# LED-mini35-SHIM.net
KiCad netlist of a schematic drawn in EAGLE
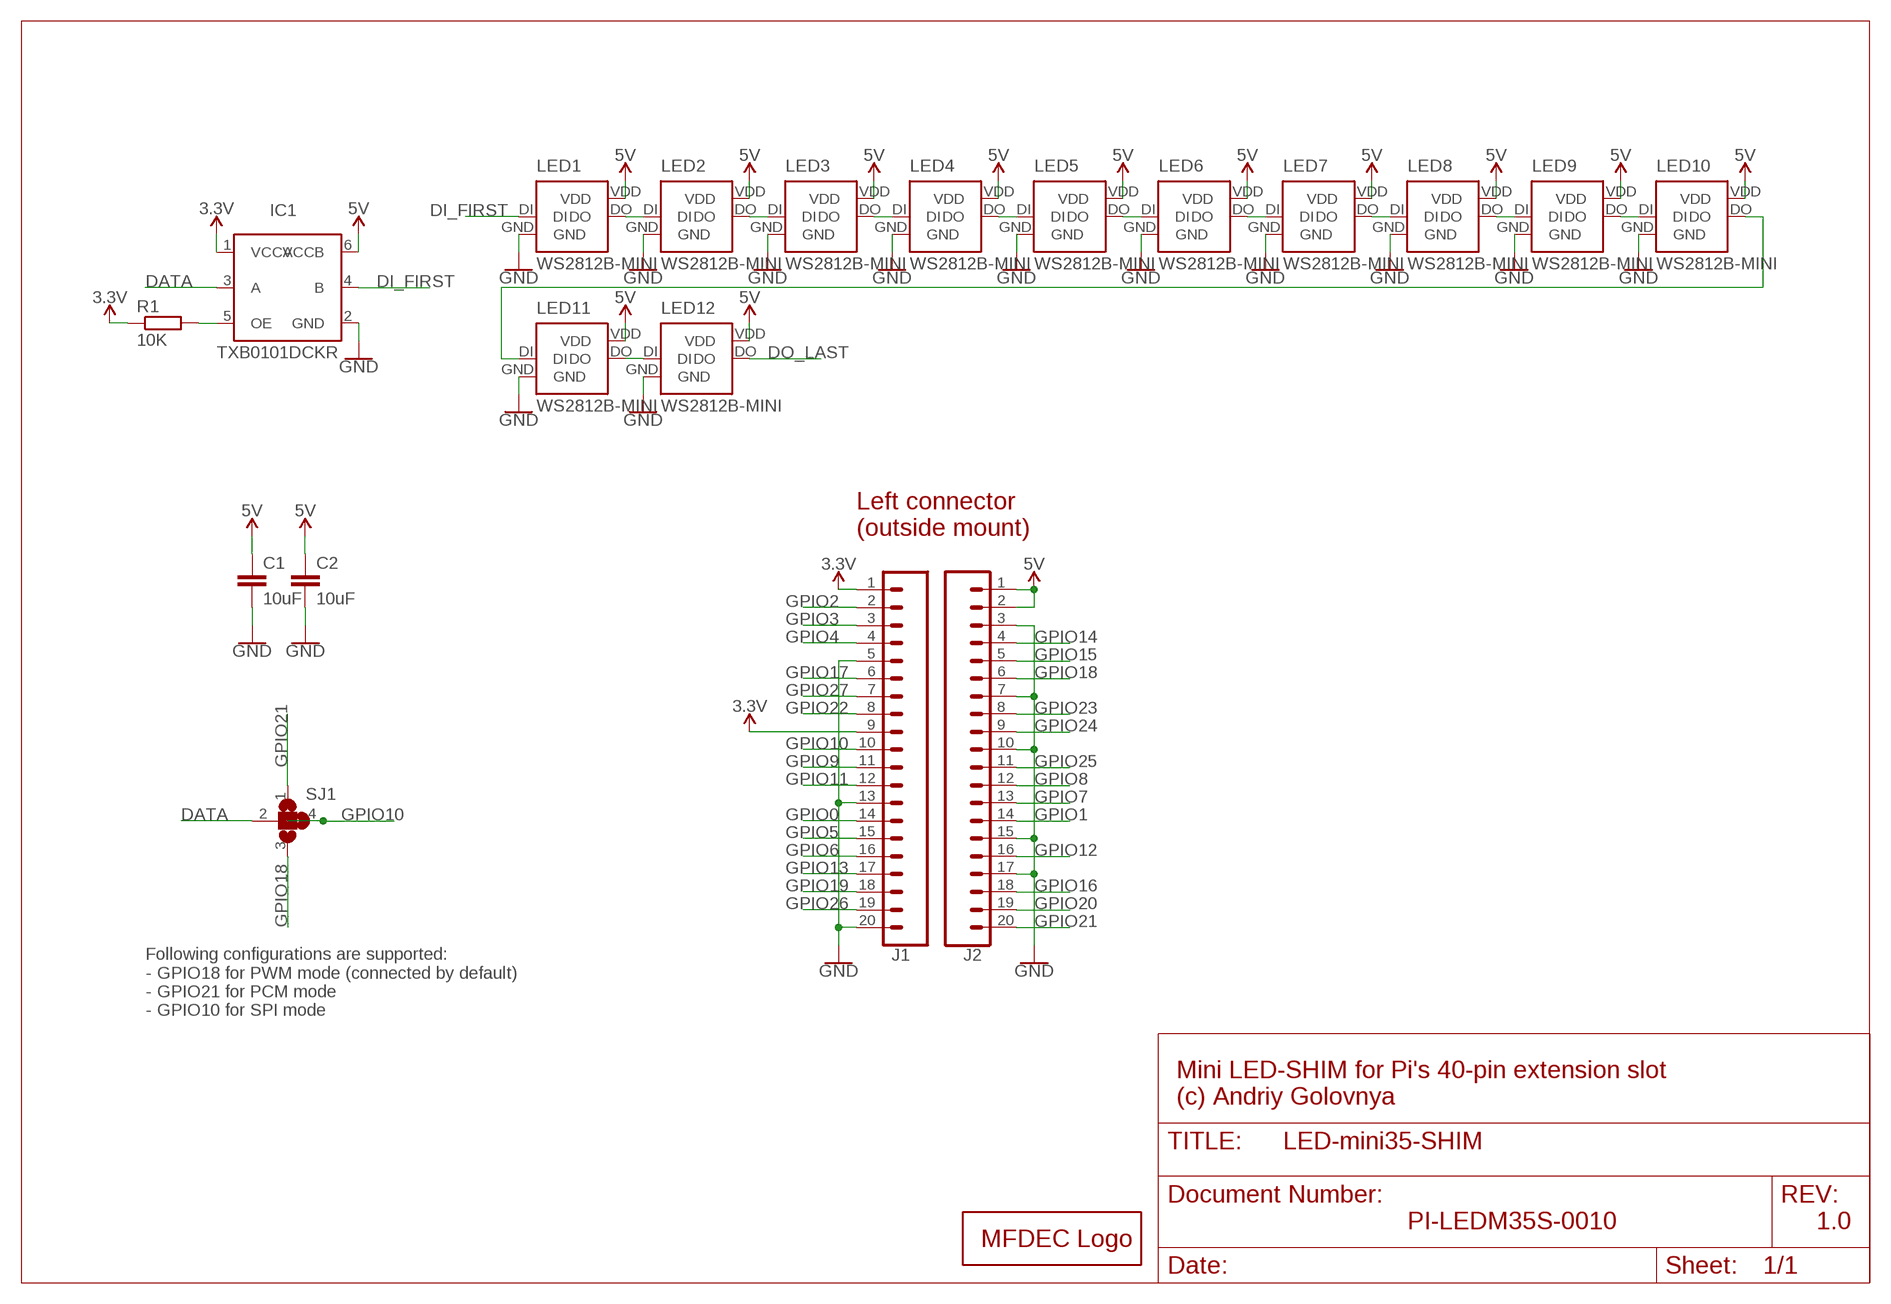
[diagram p0: schematic, sheet 1]

(export (version "E")
  (design (tool "Eeschema 10.0.6"))
  (components
    (comp (ref "C1")
      (value "10uF")
      (footprint "eagle-import:C0805")
      (libsource (lib "eagle-import") (part "C-EUC0805"))
    )
    (comp (ref "C2")
      (value "10uF")
      (footprint "eagle-import:C0805")
      (libsource (lib "eagle-import") (part "C-EUC0805"))
    )
    (comp (ref "IC1")
      (value "TXB0101DCKR")
      (footprint "eagle-import:SOT65P210X110-6N")
      (libsource (lib "eagle-import") (part "TXB0101DCKR"))
    )
    (comp (ref "J1")
      (value "CONN_20LOCK")
      (footprint "eagle-import:1X20_LOCK")
      (libsource (lib "eagle-import") (part "CONN_20LOCK"))
    )
    (comp (ref "J2")
      (value "CONN_20LOCK")
      (footprint "eagle-import:1X20_LOCK")
      (libsource (lib "eagle-import") (part "CONN_20LOCK"))
    )
    (comp (ref "LED1")
      (value "WS2812B-MINI")
      (footprint "eagle-import:WS2812X-MINI")
      (libsource (lib "eagle-import") (part "WS2812B-MINI"))
    )
    (comp (ref "LED2")
      (value "WS2812B-MINI")
      (footprint "eagle-import:WS2812X-MINI")
      (libsource (lib "eagle-import") (part "WS2812B-MINI"))
    )
    (comp (ref "LED3")
      (value "WS2812B-MINI")
      (footprint "eagle-import:WS2812X-MINI")
      (libsource (lib "eagle-import") (part "WS2812B-MINI"))
    )
    (comp (ref "LED4")
      (value "WS2812B-MINI")
      (footprint "eagle-import:WS2812X-MINI")
      (libsource (lib "eagle-import") (part "WS2812B-MINI"))
    )
    (comp (ref "LED5")
      (value "WS2812B-MINI")
      (footprint "eagle-import:WS2812X-MINI")
      (libsource (lib "eagle-import") (part "WS2812B-MINI"))
    )
    (comp (ref "LED6")
      (value "WS2812B-MINI")
      (footprint "eagle-import:WS2812X-MINI")
      (libsource (lib "eagle-import") (part "WS2812B-MINI"))
    )
    (comp (ref "LED7")
      (value "WS2812B-MINI")
      (footprint "eagle-import:WS2812X-MINI")
      (libsource (lib "eagle-import") (part "WS2812B-MINI"))
    )
    (comp (ref "LED8")
      (value "WS2812B-MINI")
      (footprint "eagle-import:WS2812X-MINI")
      (libsource (lib "eagle-import") (part "WS2812B-MINI"))
    )
    (comp (ref "LED9")
      (value "WS2812B-MINI")
      (footprint "eagle-import:WS2812X-MINI")
      (libsource (lib "eagle-import") (part "WS2812B-MINI"))
    )
    (comp (ref "LED10")
      (value "WS2812B-MINI")
      (footprint "eagle-import:WS2812X-MINI")
      (libsource (lib "eagle-import") (part "WS2812B-MINI"))
    )
    (comp (ref "LED11")
      (value "WS2812B-MINI")
      (footprint "eagle-import:WS2812X-MINI")
      (libsource (lib "eagle-import") (part "WS2812B-MINI"))
    )
    (comp (ref "LED12")
      (value "WS2812B-MINI")
      (footprint "eagle-import:WS2812X-MINI")
      (libsource (lib "eagle-import") (part "WS2812B-MINI"))
    )
    (comp (ref "LOGO1")
      (value "MFDECLOGO_L_10MM")
      (footprint "eagle-import:MFDEC_L_10MM")
      (libsource (lib "eagle-import") (part "MFDECLOGO_L_10MM"))
    )
    (comp (ref "R1")
      (value "10K")
      (footprint "eagle-import:R0402")
      (libsource (lib "eagle-import") (part "R-EU_R0402"))
    )
    (comp (ref "SJ1")
      (value "SJ3")
      (footprint "eagle-import:SJ_3")
      (libsource (lib "eagle-import") (part "SJ3"))
    )
  )
  (nets
    (net (code "1") (name "/DATA") (class "Default")
      (node (ref "IC1") (pin "3") (pinfunction "A_3") (pintype "bidirectional"))
      (node (ref "SJ1") (pin "2") (pinfunction "2_2") (pintype "passive"))
    )
    (net (code "2") (name "/DI_FIRST") (class "Default")
      (node (ref "IC1") (pin "4") (pinfunction "B_4") (pintype "bidirectional"))
      (node (ref "LED1") (pin "DI") (pinfunction "DI_DI") (pintype "input"))
    )
    (net (code "3") (name "/DO_LAST") (class "Default")
      (node (ref "LED12") (pin "DO") (pinfunction "DO_DO") (pintype "output"))
    )
    (net (code "4") (name "/GPIO0") (class "Default")
      (node (ref "J1") (pin "14") (pinfunction "14_14") (pintype "passive"))
    )
    (net (code "5") (name "/GPIO1") (class "Default")
      (node (ref "J2") (pin "14") (pinfunction "14_14") (pintype "passive"))
    )
    (net (code "6") (name "/GPIO2") (class "Default")
      (node (ref "J1") (pin "2") (pinfunction "2_2") (pintype "passive"))
    )
    (net (code "7") (name "/GPIO3") (class "Default")
      (node (ref "J1") (pin "3") (pinfunction "3_3") (pintype "passive"))
    )
    (net (code "8") (name "/GPIO4") (class "Default")
      (node (ref "J1") (pin "4") (pinfunction "4_4") (pintype "passive"))
    )
    (net (code "9") (name "/GPIO5") (class "Default")
      (node (ref "J1") (pin "15") (pinfunction "15_15") (pintype "passive"))
    )
    (net (code "10") (name "/GPIO6") (class "Default")
      (node (ref "J1") (pin "16") (pinfunction "16_16") (pintype "passive"))
    )
    (net (code "11") (name "/GPIO7") (class "Default")
      (node (ref "J2") (pin "13") (pinfunction "13_13") (pintype "passive"))
    )
    (net (code "12") (name "/GPIO8") (class "Default")
      (node (ref "J2") (pin "12") (pinfunction "12_12") (pintype "passive"))
    )
    (net (code "13") (name "/GPIO9") (class "Default")
      (node (ref "J1") (pin "11") (pinfunction "11_11") (pintype "passive"))
    )
    (net (code "14") (name "/GPIO10") (class "Default")
      (node (ref "J1") (pin "10") (pinfunction "10_10") (pintype "passive"))
      (node (ref "SJ1") (pin "4") (pinfunction "4_4") (pintype "passive"))
    )
    (net (code "15") (name "/GPIO11") (class "Default")
      (node (ref "J1") (pin "12") (pinfunction "12_12") (pintype "passive"))
    )
    (net (code "16") (name "/GPIO12") (class "Default")
      (node (ref "J2") (pin "16") (pinfunction "16_16") (pintype "passive"))
    )
    (net (code "17") (name "/GPIO13") (class "Default")
      (node (ref "J1") (pin "17") (pinfunction "17_17") (pintype "passive"))
    )
    (net (code "18") (name "/GPIO14") (class "Default")
      (node (ref "J2") (pin "4") (pinfunction "4_4") (pintype "passive"))
    )
    (net (code "19") (name "/GPIO15") (class "Default")
      (node (ref "J2") (pin "5") (pinfunction "5_5") (pintype "passive"))
    )
    (net (code "20") (name "/GPIO16") (class "Default")
      (node (ref "J2") (pin "18") (pinfunction "18_18") (pintype "passive"))
    )
    (net (code "21") (name "/GPIO17") (class "Default")
      (node (ref "J1") (pin "6") (pinfunction "6_6") (pintype "passive"))
    )
    (net (code "22") (name "/GPIO18") (class "Default")
      (node (ref "J2") (pin "6") (pinfunction "6_6") (pintype "passive"))
      (node (ref "SJ1") (pin "3") (pinfunction "3_3") (pintype "passive"))
    )
    (net (code "23") (name "/GPIO19") (class "Default")
      (node (ref "J1") (pin "18") (pinfunction "18_18") (pintype "passive"))
    )
    (net (code "24") (name "/GPIO20") (class "Default")
      (node (ref "J2") (pin "19") (pinfunction "19_19") (pintype "passive"))
    )
    (net (code "25") (name "/GPIO21") (class "Default")
      (node (ref "J2") (pin "20") (pinfunction "20_20") (pintype "passive"))
      (node (ref "SJ1") (pin "1") (pinfunction "1_1") (pintype "passive"))
    )
    (net (code "26") (name "/GPIO22") (class "Default")
      (node (ref "J1") (pin "8") (pinfunction "8_8") (pintype "passive"))
    )
    (net (code "27") (name "/GPIO23") (class "Default")
      (node (ref "J2") (pin "8") (pinfunction "8_8") (pintype "passive"))
    )
    (net (code "28") (name "/GPIO24") (class "Default")
      (node (ref "J2") (pin "9") (pinfunction "9_9") (pintype "passive"))
    )
    (net (code "29") (name "/GPIO25") (class "Default")
      (node (ref "J2") (pin "11") (pinfunction "11_11") (pintype "passive"))
    )
    (net (code "30") (name "/GPIO26") (class "Default")
      (node (ref "J1") (pin "19") (pinfunction "19_19") (pintype "passive"))
    )
    (net (code "31") (name "/GPIO27") (class "Default")
      (node (ref "J1") (pin "7") (pinfunction "7_7") (pintype "passive"))
    )
    (net (code "32") (name "3.3V") (class "Default")
      (node (ref "IC1") (pin "1") (pinfunction "VCCA_1") (pintype "power_in"))
      (node (ref "J1") (pin "1") (pinfunction "1_1") (pintype "passive"))
      (node (ref "J1") (pin "9") (pinfunction "9_9") (pintype "passive"))
      (node (ref "R1") (pin "1") (pinfunction "1_1") (pintype "passive"))
    )
    (net (code "33") (name "5V") (class "Default")
      (node (ref "C1") (pin "1") (pinfunction "1_1") (pintype "passive"))
      (node (ref "C2") (pin "1") (pinfunction "1_1") (pintype "passive"))
      (node (ref "IC1") (pin "6") (pinfunction "VCCB_6") (pintype "power_in"))
      (node (ref "J2") (pin "1") (pinfunction "1_1") (pintype "passive"))
      (node (ref "J2") (pin "2") (pinfunction "2_2") (pintype "passive"))
      (node (ref "LED1") (pin "VDD") (pinfunction "VDD_VDD") (pintype "power_in"))
      (node (ref "LED10") (pin "VDD") (pinfunction "VDD_VDD") (pintype "power_in"))
      (node (ref "LED11") (pin "VDD") (pinfunction "VDD_VDD") (pintype "power_in"))
      (node (ref "LED12") (pin "VDD") (pinfunction "VDD_VDD") (pintype "power_in"))
      (node (ref "LED2") (pin "VDD") (pinfunction "VDD_VDD") (pintype "power_in"))
      (node (ref "LED3") (pin "VDD") (pinfunction "VDD_VDD") (pintype "power_in"))
      (node (ref "LED4") (pin "VDD") (pinfunction "VDD_VDD") (pintype "power_in"))
      (node (ref "LED5") (pin "VDD") (pinfunction "VDD_VDD") (pintype "power_in"))
      (node (ref "LED6") (pin "VDD") (pinfunction "VDD_VDD") (pintype "power_in"))
      (node (ref "LED7") (pin "VDD") (pinfunction "VDD_VDD") (pintype "power_in"))
      (node (ref "LED8") (pin "VDD") (pinfunction "VDD_VDD") (pintype "power_in"))
      (node (ref "LED9") (pin "VDD") (pinfunction "VDD_VDD") (pintype "power_in"))
    )
    (net (code "34") (name "GND") (class "Default")
      (node (ref "C1") (pin "2") (pinfunction "2_2") (pintype "passive"))
      (node (ref "C2") (pin "2") (pinfunction "2_2") (pintype "passive"))
      (node (ref "IC1") (pin "2") (pinfunction "GND_2") (pintype "power_in"))
      (node (ref "J1") (pin "13") (pinfunction "13_13") (pintype "passive"))
      (node (ref "J1") (pin "20") (pinfunction "20_20") (pintype "passive"))
      (node (ref "J1") (pin "5") (pinfunction "5_5") (pintype "passive"))
      (node (ref "J2") (pin "10") (pinfunction "10_10") (pintype "passive"))
      (node (ref "J2") (pin "15") (pinfunction "15_15") (pintype "passive"))
      (node (ref "J2") (pin "17") (pinfunction "17_17") (pintype "passive"))
      (node (ref "J2") (pin "3") (pinfunction "3_3") (pintype "passive"))
      (node (ref "J2") (pin "7") (pinfunction "7_7") (pintype "passive"))
      (node (ref "LED1") (pin "GND") (pinfunction "GND_GND") (pintype "power_in"))
      (node (ref "LED10") (pin "GND") (pinfunction "GND_GND") (pintype "power_in"))
      (node (ref "LED11") (pin "GND") (pinfunction "GND_GND") (pintype "power_in"))
      (node (ref "LED12") (pin "GND") (pinfunction "GND_GND") (pintype "power_in"))
      (node (ref "LED2") (pin "GND") (pinfunction "GND_GND") (pintype "power_in"))
      (node (ref "LED3") (pin "GND") (pinfunction "GND_GND") (pintype "power_in"))
      (node (ref "LED4") (pin "GND") (pinfunction "GND_GND") (pintype "power_in"))
      (node (ref "LED5") (pin "GND") (pinfunction "GND_GND") (pintype "power_in"))
      (node (ref "LED6") (pin "GND") (pinfunction "GND_GND") (pintype "power_in"))
      (node (ref "LED7") (pin "GND") (pinfunction "GND_GND") (pintype "power_in"))
      (node (ref "LED8") (pin "GND") (pinfunction "GND_GND") (pintype "power_in"))
      (node (ref "LED9") (pin "GND") (pinfunction "GND_GND") (pintype "power_in"))
    )
    (net (code "35") (name "Net-(IC1-OE)") (class "Default")
      (node (ref "IC1") (pin "5") (pinfunction "OE_5") (pintype "input"))
      (node (ref "R1") (pin "2") (pinfunction "2_2") (pintype "passive"))
    )
    (net (code "36") (name "Net-(LED1-PadDO)") (class "Default")
      (node (ref "LED1") (pin "DO") (pinfunction "DO_DO") (pintype "output"))
      (node (ref "LED2") (pin "DI") (pinfunction "DI_DI") (pintype "input"))
    )
    (net (code "37") (name "Net-(LED2-PadDO)") (class "Default")
      (node (ref "LED2") (pin "DO") (pinfunction "DO_DO") (pintype "output"))
      (node (ref "LED3") (pin "DI") (pinfunction "DI_DI") (pintype "input"))
    )
    (net (code "38") (name "Net-(LED3-PadDO)") (class "Default")
      (node (ref "LED3") (pin "DO") (pinfunction "DO_DO") (pintype "output"))
      (node (ref "LED4") (pin "DI") (pinfunction "DI_DI") (pintype "input"))
    )
    (net (code "39") (name "Net-(LED4-PadDO)") (class "Default")
      (node (ref "LED4") (pin "DO") (pinfunction "DO_DO") (pintype "output"))
      (node (ref "LED5") (pin "DI") (pinfunction "DI_DI") (pintype "input"))
    )
    (net (code "40") (name "Net-(LED5-PadDO)") (class "Default")
      (node (ref "LED5") (pin "DO") (pinfunction "DO_DO") (pintype "output"))
      (node (ref "LED6") (pin "DI") (pinfunction "DI_DI") (pintype "input"))
    )
    (net (code "41") (name "Net-(LED6-PadDO)") (class "Default")
      (node (ref "LED6") (pin "DO") (pinfunction "DO_DO") (pintype "output"))
      (node (ref "LED7") (pin "DI") (pinfunction "DI_DI") (pintype "input"))
    )
    (net (code "42") (name "Net-(LED7-PadDO)") (class "Default")
      (node (ref "LED7") (pin "DO") (pinfunction "DO_DO") (pintype "output"))
      (node (ref "LED8") (pin "DI") (pinfunction "DI_DI") (pintype "input"))
    )
    (net (code "43") (name "Net-(LED8-PadDO)") (class "Default")
      (node (ref "LED8") (pin "DO") (pinfunction "DO_DO") (pintype "output"))
      (node (ref "LED9") (pin "DI") (pinfunction "DI_DI") (pintype "input"))
    )
    (net (code "44") (name "Net-(LED10-PadDI)") (class "Default")
      (node (ref "LED10") (pin "DI") (pinfunction "DI_DI") (pintype "input"))
      (node (ref "LED9") (pin "DO") (pinfunction "DO_DO") (pintype "output"))
    )
    (net (code "45") (name "Net-(LED10-PadDO)") (class "Default")
      (node (ref "LED10") (pin "DO") (pinfunction "DO_DO") (pintype "output"))
      (node (ref "LED11") (pin "DI") (pinfunction "DI_DI") (pintype "input"))
    )
    (net (code "46") (name "Net-(LED11-PadDO)") (class "Default")
      (node (ref "LED11") (pin "DO") (pinfunction "DO_DO") (pintype "output"))
      (node (ref "LED12") (pin "DI") (pinfunction "DI_DI") (pintype "input"))
    )
  )
)
